# 4_IMU.net
KiCad netlist of a schematic drawn in Altium Designer
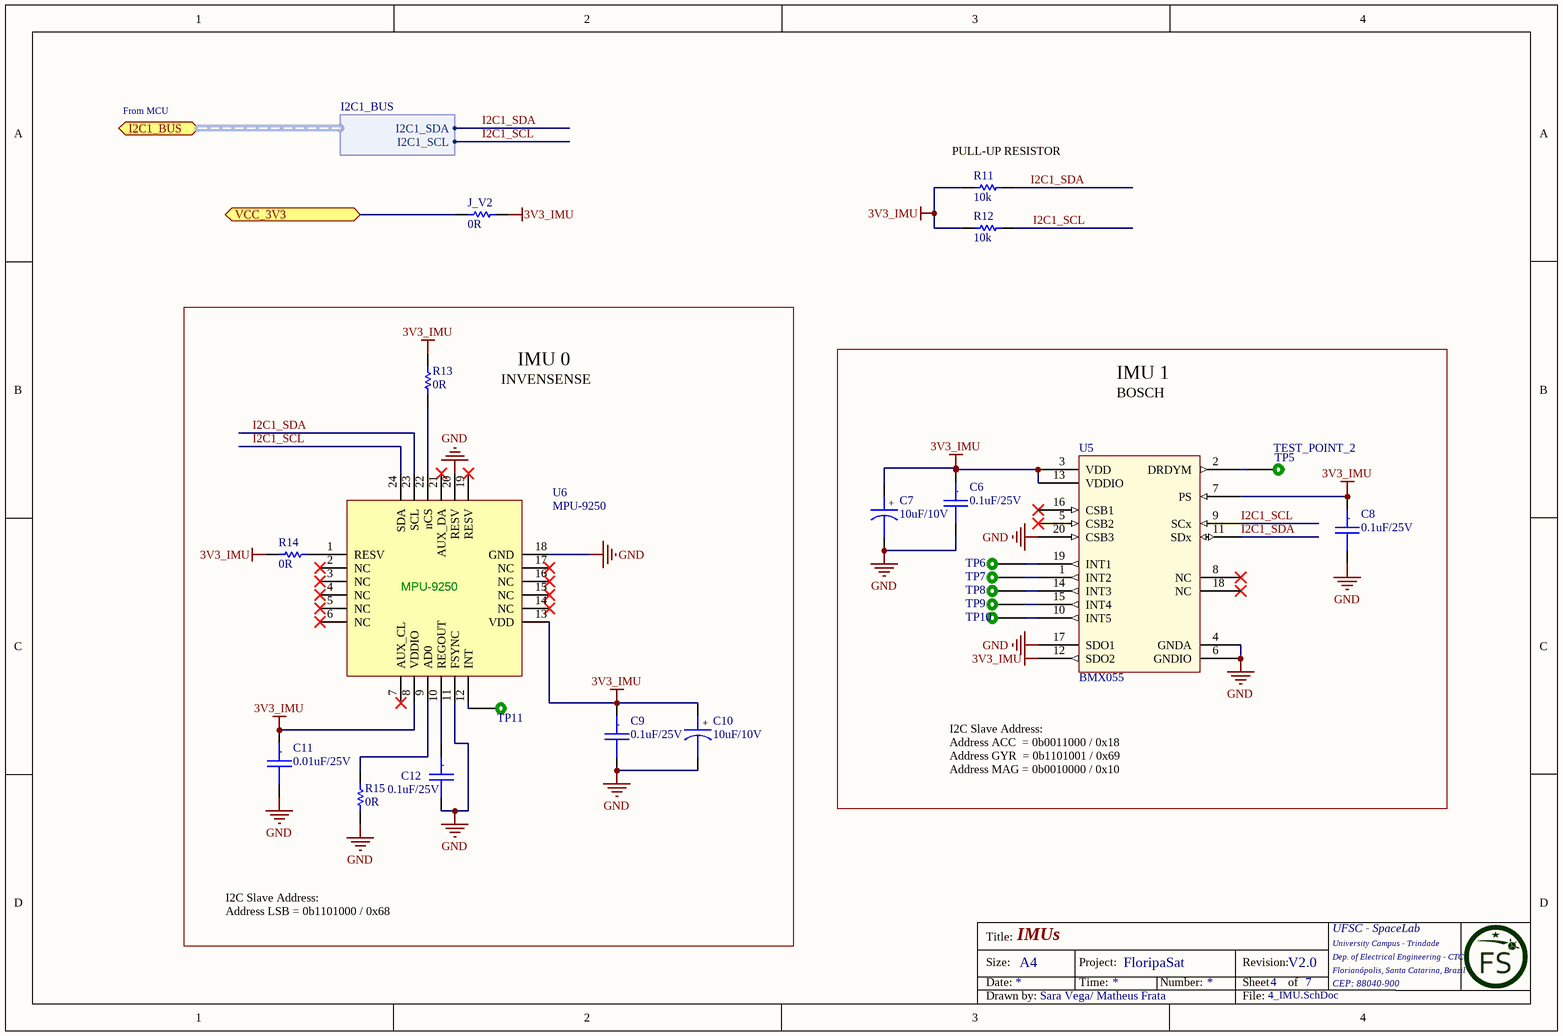
[diagram p0: 4_IMU.SchDoc]

(export (version "E")
  (design (tool "Eeschema 10.0.6"))
  (components
    (comp (ref "C6")
      (value "0.1uF/25V")
      (footprint "CC0805")
      (description "CAP CER 0.1UF 25V 10% X7R 0805")
      (fields (field (name "PARTNUMBER") "CC0805KRX7R8BB104"))
      (libsource (lib "FloripaSatSchlib") (part "Cap_Cer_X7R_0.1uF_25V_0805"))
    )
    (comp (ref "C7")
      (value "10uF/10V")
      (footprint "FloripaSatPcbLib:CC0805_Tantalum")
      (description "CAP Tantalum 10uF 10V 20% 0805")
      (fields (field (name "PARTNUMBER") "TPSP106M010R2000"))
      (libsource (lib "FloripaSatSchlib") (part "Cap_Tant_SMD_10uF_10V_0805"))
    )
    (comp (ref "C8")
      (value "0.1uF/25V")
      (footprint "CC0805")
      (description "CAP CER 0.1UF 25V 10% X7R 0805")
      (fields (field (name "PARTNUMBER") "CC0805KRX7R8BB104"))
      (libsource (lib "FloripaSatSchlib") (part "Cap_Cer_X7R_0.1uF_25V_0805"))
    )
    (comp (ref "C9")
      (value "0.1uF/25V")
      (footprint "CC0805")
      (description "CAP CER 0.1UF 25V 10% X7R 0805")
      (fields (field (name "PARTNUMBER") "CC0805KRX7R8BB104"))
      (libsource (lib "FloripaSatSchlib") (part "Cap_Cer_X7R_0.1uF_25V_0805"))
    )
    (comp (ref "C10")
      (value "10uF/10V")
      (footprint "FloripaSatPcbLib:CC0805_Tantalum")
      (description "CAP Tantalum 10uF 10V 20% 0805")
      (fields (field (name "PARTNUMBER") "TPSP106M010R2000"))
      (libsource (lib "FloripaSatSchlib") (part "Cap_Tant_SMD_10uF_10V_0805"))
    )
    (comp (ref "C11")
      (value "0.01uF/25V")
      (footprint "CC0805")
      (description "CAP CER 0.01uF 25V 10% X7R 0805")
      (fields (field (name "PARTNUMBER") "CL21B103KAANNNC"))
      (libsource (lib "FloripaSatSchlib") (part "Cap_Cer_X7R_0.01uF_50V_0805"))
    )
    (comp (ref "C12")
      (value "0.1uF/25V")
      (footprint "CC0805")
      (description "CAP CER 0.1UF 25V 10% X7R 0805")
      (fields (field (name "PARTNUMBER") "CC0805KRX7R8BB104"))
      (libsource (lib "FloripaSatSchlib") (part "Cap_Cer_X7R_0.1uF_25V_0805"))
    )
    (comp (ref "J_V2")
      (value "0R")
      (footprint "FloripaSatPcbLib:0805")
      (description "RES 0R OHM 1/16W JUMPER 0805")
      (fields (field (name "PARTNUMBER") "CRCW08050000Z0EA"))
      (libsource (lib "FloripaSatSchlib") (part "R0R_JUMPER_1/16W_0805"))
    )
    (comp (ref "R11")
      (value "10k")
      (footprint "0805")
      (description "RES 10K OHM 1/8W 1%  0805")
      (fields (field (name "PARTNUMBER") "CRCW080510K0FKEA"))
      (libsource (lib "FloripaSatSchlib") (part "R10k_1%_1/8W_0805"))
    )
    (comp (ref "R12")
      (value "10k")
      (footprint "0805")
      (description "RES 10K OHM 1/8W 1%  0805")
      (fields (field (name "PARTNUMBER") "CRCW080510K0FKEA"))
      (libsource (lib "FloripaSatSchlib") (part "R10k_1%_1/8W_0805"))
    )
    (comp (ref "R13")
      (value "0R")
      (footprint "FloripaSatPcbLib:0805")
      (description "RES 0R OHM 1/16W JUMPER 0805")
      (fields (field (name "PARTNUMBER") "CRCW08050000Z0EA"))
      (libsource (lib "FloripaSatSchlib") (part "R0R_JUMPER_1/16W_0805"))
    )
    (comp (ref "R14")
      (value "0R")
      (footprint "FloripaSatPcbLib:0805")
      (description "RES 0R OHM 1/16W JUMPER 0805")
      (fields (field (name "PARTNUMBER") "CRCW08050000Z0EA"))
      (libsource (lib "FloripaSatSchlib") (part "R0R_JUMPER_1/16W_0805"))
    )
    (comp (ref "R15")
      (value "0R")
      (footprint "FloripaSatPcbLib:0805")
      (description "RES 0R OHM 1/16W JUMPER 0805")
      (fields (field (name "PARTNUMBER") "CRCW08050000Z0EA"))
      (libsource (lib "FloripaSatSchlib") (part "R0R_JUMPER_1/16W_0805"))
    )
    (comp (ref "TP5")
      (value "TEST_POINT_2")
      (footprint "TEST_POINT_2")
      (description "Test point")
      (libsource (lib "FloripaSatSchlib") (part "TEST_POINT_2"))
    )
    (comp (ref "TP6")
      (value "TEST_POINT_2")
      (footprint "TEST_POINT_2")
      (description "Test point")
      (libsource (lib "FloripaSatSchlib") (part "TEST_POINT_2"))
    )
    (comp (ref "TP7")
      (value "TEST_POINT_2")
      (footprint "TEST_POINT_2")
      (description "Test point")
      (libsource (lib "FloripaSatSchlib") (part "TEST_POINT_2"))
    )
    (comp (ref "TP8")
      (value "TEST_POINT_2")
      (footprint "TEST_POINT_2")
      (description "Test point")
      (libsource (lib "FloripaSatSchlib") (part "TEST_POINT_2"))
    )
    (comp (ref "TP9")
      (value "TEST_POINT_2")
      (footprint "TEST_POINT_2")
      (description "Test point")
      (libsource (lib "FloripaSatSchlib") (part "TEST_POINT_2"))
    )
    (comp (ref "TP10")
      (value "TEST_POINT_2")
      (footprint "TEST_POINT_2")
      (description "Test point")
      (libsource (lib "FloripaSatSchlib") (part "TEST_POINT_2"))
    )
    (comp (ref "TP11")
      (value "TEST_POINT_2")
      (footprint "TEST_POINT_2")
      (description "Test point")
      (libsource (lib "FloripaSatSchlib") (part "TEST_POINT_2"))
    )
    (comp (ref "U5")
      (value "BMX055")
      (footprint "LGA20")
      (libsource (lib "FloripaSatSchlib") (part "BMX055"))
    )
    (comp (ref "U6")
      (value "MPU-9250")
      (footprint "QFN24P300X300X105-25N")
      (description "SMD Gyroscope/Accelerometer/Magnetometer Sensor; 9-AXIS")
      (libsource (lib "FloripaSatSchlib") (part "MPU9250"))
    )
  )
  (nets
    (net (code "2") (name "/I2C1_SCL") (class "Default")
      (node (ref "R12") (pin "1") (pinfunction "1_1") (pintype "passive"))
      (node (ref "U5") (pin "9") (pinfunction "SCx_9") (pintype "input"))
      (node (ref "U6") (pin "24") (pinfunction "SDA_24") (pintype "passive"))
    )
    (net (code "3") (name "/I2C1_SDA") (class "Default")
      (node (ref "R11") (pin "1") (pinfunction "1_1") (pintype "passive"))
      (node (ref "U5") (pin "11") (pinfunction "SDx_11") (pintype "bidirectional"))
      (node (ref "U6") (pin "23") (pinfunction "SCL_23") (pintype "passive"))
    )
    (net (code "4") (name "/VCC_3V3") (class "Default")
      (node (ref "J_V2") (pin "2") (pinfunction "2_2") (pintype "passive"))
    )
    (net (code "6") (name "3V3_IMU") (class "Default")
      (node (ref "C10") (pin "1") (pinfunction "1_1") (pintype "passive"))
      (node (ref "C11") (pin "1") (pinfunction "1_1") (pintype "passive"))
      (node (ref "C6") (pin "1") (pinfunction "1_1") (pintype "passive"))
      (node (ref "C7") (pin "1") (pinfunction "1_1") (pintype "passive"))
      (node (ref "C8") (pin "1") (pinfunction "1_1") (pintype "passive"))
      (node (ref "C9") (pin "1") (pinfunction "1_1") (pintype "passive"))
      (node (ref "J_V2") (pin "1") (pinfunction "1_1") (pintype "passive"))
      (node (ref "R11") (pin "2") (pinfunction "2_2") (pintype "passive"))
      (node (ref "R12") (pin "2") (pinfunction "2_2") (pintype "passive"))
      (node (ref "R13") (pin "2") (pinfunction "2_2") (pintype "passive"))
      (node (ref "R14") (pin "2") (pinfunction "2_2") (pintype "passive"))
      (node (ref "U5") (pin "12") (pinfunction "SDO2_12") (pintype "output"))
      (node (ref "U5") (pin "13") (pinfunction "VDDIO_13") (pintype "passive"))
      (node (ref "U5") (pin "3") (pinfunction "VDD_3") (pintype "passive"))
      (node (ref "U5") (pin "7") (pinfunction "PS_7") (pintype "input"))
      (node (ref "U6") (pin "13") (pinfunction "VDD_13") (pintype "passive"))
      (node (ref "U6") (pin "8") (pinfunction "VDDIO_8") (pintype "passive"))
    )
    (net (code "7") (name "GND") (class "Default")
      (node (ref "C10") (pin "2") (pinfunction "2_2") (pintype "passive"))
      (node (ref "C11") (pin "2") (pinfunction "2_2") (pintype "passive"))
      (node (ref "C12") (pin "2") (pinfunction "2_2") (pintype "passive"))
      (node (ref "C6") (pin "2") (pinfunction "2_2") (pintype "passive"))
      (node (ref "C7") (pin "2") (pinfunction "2_2") (pintype "passive"))
      (node (ref "C8") (pin "2") (pinfunction "2_2") (pintype "passive"))
      (node (ref "C9") (pin "2") (pinfunction "2_2") (pintype "passive"))
      (node (ref "R15") (pin "2") (pinfunction "2_2") (pintype "passive"))
      (node (ref "U5") (pin "17") (pinfunction "SDO1_17") (pintype "passive"))
      (node (ref "U5") (pin "20") (pinfunction "CSB3_20") (pintype "input"))
      (node (ref "U5") (pin "4") (pinfunction "GNDA_4") (pintype "passive"))
      (node (ref "U5") (pin "6") (pinfunction "GNDIO_6") (pintype "passive"))
      (node (ref "U6") (pin "11") (pinfunction "FSYNC_11") (pintype "passive"))
      (node (ref "U6") (pin "18") (pinfunction "GND_18") (pintype "passive"))
      (node (ref "U6") (pin "20") (pinfunction "RESV_20") (pintype "passive"))
    )
    (net (code "8") (name "Net-(R14-Pad1)") (class "Default")
      (node (ref "R14") (pin "1") (pinfunction "1_1") (pintype "passive"))
      (node (ref "U6") (pin "1") (pinfunction "RESV_1") (pintype "passive"))
    )
    (net (code "9") (name "Net-(U5-DRDYM)") (class "Default")
      (node (ref "TP5") (pin "1") (pinfunction "1_1") (pintype "passive"))
      (node (ref "U5") (pin "2") (pinfunction "DRDYM_2") (pintype "output"))
    )
    (net (code "10") (name "Net-(U5-INT1)") (class "Default")
      (node (ref "TP6") (pin "1") (pinfunction "1_1") (pintype "passive"))
      (node (ref "U5") (pin "19") (pinfunction "INT1_19") (pintype "output"))
    )
    (net (code "11") (name "Net-(U5-INT2)") (class "Default")
      (node (ref "TP7") (pin "1") (pinfunction "1_1") (pintype "passive"))
      (node (ref "U5") (pin "1") (pinfunction "INT2_1") (pintype "output"))
    )
    (net (code "12") (name "Net-(U5-INT3)") (class "Default")
      (node (ref "TP8") (pin "1") (pinfunction "1_1") (pintype "passive"))
      (node (ref "U5") (pin "14") (pinfunction "INT3_14") (pintype "output"))
    )
    (net (code "13") (name "Net-(U5-INT4)") (class "Default")
      (node (ref "TP9") (pin "1") (pinfunction "1_1") (pintype "passive"))
      (node (ref "U5") (pin "15") (pinfunction "INT4_15") (pintype "output"))
    )
    (net (code "14") (name "Net-(U5-INT5)") (class "Default")
      (node (ref "TP10") (pin "1") (pinfunction "1_1") (pintype "passive"))
      (node (ref "U5") (pin "10") (pinfunction "INT5_10") (pintype "output"))
    )
    (net (code "15") (name "Net-(U6-AD0)") (class "Default")
      (node (ref "R15") (pin "1") (pinfunction "1_1") (pintype "passive"))
      (node (ref "U6") (pin "9") (pinfunction "AD0_9") (pintype "passive"))
    )
    (net (code "16") (name "Net-(U6-INT)") (class "Default")
      (node (ref "TP11") (pin "1") (pinfunction "1_1") (pintype "passive"))
      (node (ref "U6") (pin "12") (pinfunction "INT_12") (pintype "passive"))
    )
    (net (code "17") (name "Net-(U6-REGOUT)") (class "Default")
      (node (ref "C12") (pin "1") (pinfunction "1_1") (pintype "passive"))
      (node (ref "U6") (pin "10") (pinfunction "REGOUT_10") (pintype "passive"))
    )
    (net (code "18") (name "Net-(U6-nCS)") (class "Default")
      (node (ref "R13") (pin "1") (pinfunction "1_1") (pintype "passive"))
      (node (ref "U6") (pin "22") (pinfunction "nCS_22") (pintype "passive"))
    )
    (net (code "19") (name "unconnected-(U5-CSB1-Pad16)") (class "Default")
      (node (ref "U5") (pin "16") (pinfunction "CSB1_16") (pintype "input+no_connect"))
    )
    (net (code "20") (name "unconnected-(U5-CSB2-Pad5)") (class "Default")
      (node (ref "U5") (pin "5") (pinfunction "CSB2_5") (pintype "input+no_connect"))
    )
    (net (code "21") (name "unconnected-(U5-NC-Pad8)") (class "Default")
      (node (ref "U5") (pin "8") (pinfunction "NC_8") (pintype "passive+no_connect"))
    )
    (net (code "22") (name "unconnected-(U5-NC-Pad18)") (class "Default")
      (node (ref "U5") (pin "18") (pinfunction "NC_18") (pintype "passive+no_connect"))
    )
    (net (code "23") (name "unconnected-(U6-AUX_CL-Pad7)") (class "Default")
      (node (ref "U6") (pin "7") (pinfunction "AUX_CL_7") (pintype "passive+no_connect"))
    )
    (net (code "24") (name "unconnected-(U6-AUX_DA-Pad21)") (class "Default")
      (node (ref "U6") (pin "21") (pinfunction "AUX_DA_21") (pintype "passive+no_connect"))
    )
    (net (code "25") (name "unconnected-(U6-NC-Pad2)") (class "Default")
      (node (ref "U6") (pin "2") (pinfunction "NC_2") (pintype "passive+no_connect"))
    )
    (net (code "26") (name "unconnected-(U6-NC-Pad3)") (class "Default")
      (node (ref "U6") (pin "3") (pinfunction "NC_3") (pintype "passive+no_connect"))
    )
    (net (code "27") (name "unconnected-(U6-NC-Pad4)") (class "Default")
      (node (ref "U6") (pin "4") (pinfunction "NC_4") (pintype "passive+no_connect"))
    )
    (net (code "28") (name "unconnected-(U6-NC-Pad5)") (class "Default")
      (node (ref "U6") (pin "5") (pinfunction "NC_5") (pintype "passive+no_connect"))
    )
    (net (code "29") (name "unconnected-(U6-NC-Pad6)") (class "Default")
      (node (ref "U6") (pin "6") (pinfunction "NC_6") (pintype "passive+no_connect"))
    )
    (net (code "30") (name "unconnected-(U6-NC-Pad14)") (class "Default")
      (node (ref "U6") (pin "14") (pinfunction "NC_14") (pintype "passive+no_connect"))
    )
    (net (code "31") (name "unconnected-(U6-NC-Pad15)") (class "Default")
      (node (ref "U6") (pin "15") (pinfunction "NC_15") (pintype "passive+no_connect"))
    )
    (net (code "32") (name "unconnected-(U6-NC-Pad16)") (class "Default")
      (node (ref "U6") (pin "16") (pinfunction "NC_16") (pintype "passive+no_connect"))
    )
    (net (code "33") (name "unconnected-(U6-NC-Pad17)") (class "Default")
      (node (ref "U6") (pin "17") (pinfunction "NC_17") (pintype "passive+no_connect"))
    )
    (net (code "34") (name "unconnected-(U6-RESV-Pad19)") (class "Default")
      (node (ref "U6") (pin "19") (pinfunction "RESV_19") (pintype "passive+no_connect"))
    )
  )
)
